# PixelController_V04.net
KiCad netlist of a schematic drawn in EAGLE
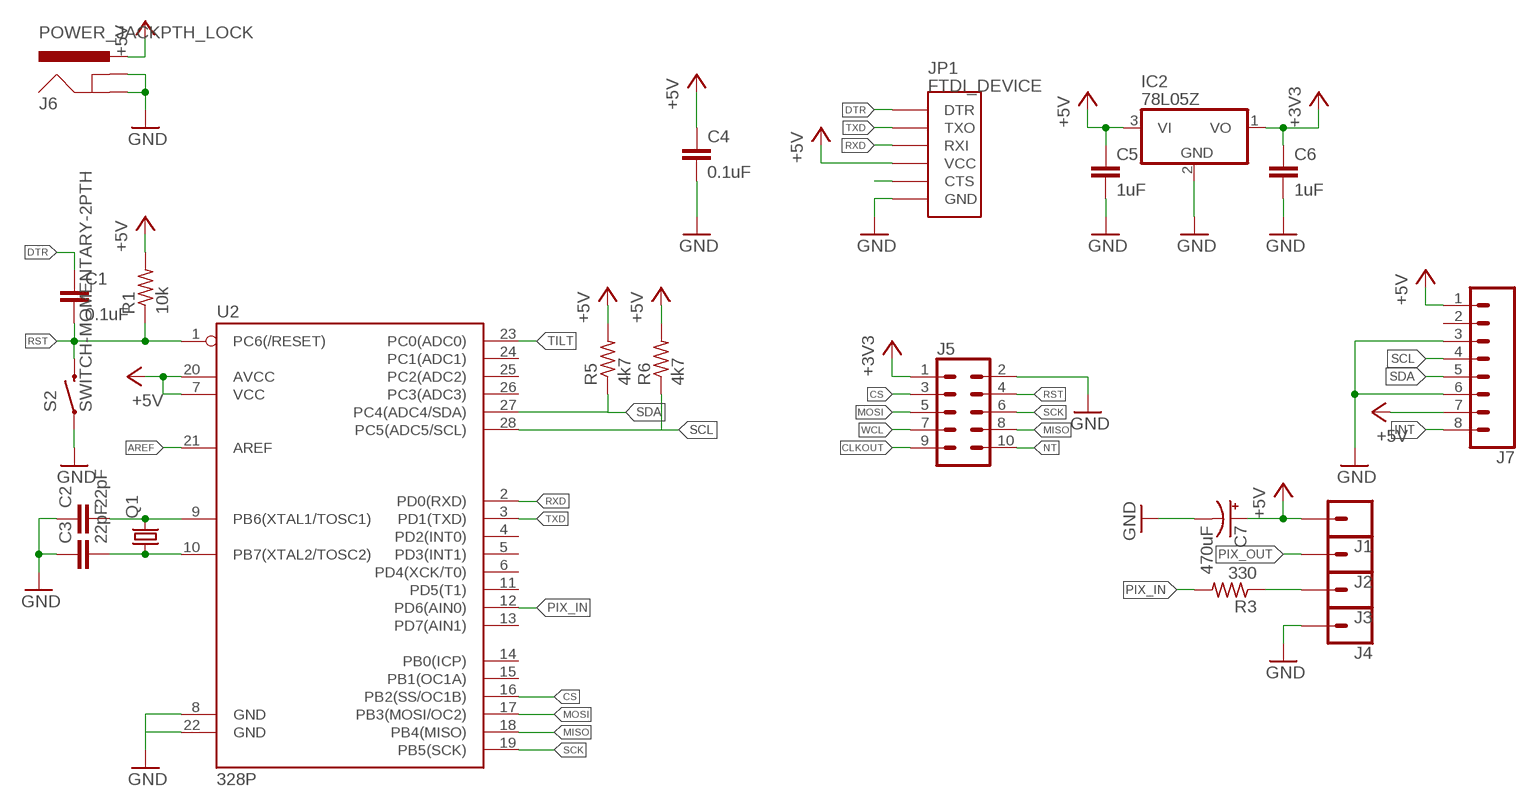
[diagram p0: schematic, sheet 1]

(export (version "E")
  (design (tool "Eeschema 10.0.6"))
  (components
    (comp (ref "C1")
      (value "0.1uF")
      (footprint "eagle-import:C050-025X075")
      (libsource (lib "eagle-import") (part "C-EU050-025X075"))
    )
    (comp (ref "C2")
      (value "22pF")
      (footprint "eagle-import:C050-024X044")
      (libsource (lib "eagle-import") (part "C-EU050-024X044"))
    )
    (comp (ref "C3")
      (value "22pF")
      (footprint "eagle-import:C050-024X044")
      (libsource (lib "eagle-import") (part "C-EU050-024X044"))
    )
    (comp (ref "C4")
      (value "0.1uF")
      (footprint "eagle-import:C050-025X075")
      (libsource (lib "eagle-import") (part "C-EU050-025X075"))
    )
    (comp (ref "C5")
      (value "1uF")
      (footprint "eagle-import:C050-025X075")
      (libsource (lib "eagle-import") (part "C-EU050-025X075"))
    )
    (comp (ref "C6")
      (value "1uF")
      (footprint "eagle-import:C050-025X075")
      (libsource (lib "eagle-import") (part "C-EU050-025X075"))
    )
    (comp (ref "C7")
      (value "470uF")
      (footprint "eagle-import:E3,5-8")
      (libsource (lib "eagle-import") (part "CPOL-USE3.5-8"))
    )
    (comp (ref "IC2")
      (value "78L05Z")
      (footprint "eagle-import:TO92")
      (libsource (lib "eagle-import") (part "78ZL05"))
    )
    (comp (ref "J1")
      (value "CONN_01")
      (footprint "eagle-import:1X01")
      (libsource (lib "eagle-import") (part "CONN_01"))
    )
    (comp (ref "J2")
      (value "CONN_01")
      (footprint "eagle-import:1X01")
      (libsource (lib "eagle-import") (part "CONN_01"))
    )
    (comp (ref "J3")
      (value "CONN_01")
      (footprint "eagle-import:1X01")
      (libsource (lib "eagle-import") (part "CONN_01"))
    )
    (comp (ref "J4")
      (value "CONN_01")
      (footprint "eagle-import:1X01")
      (libsource (lib "eagle-import") (part "CONN_01"))
    )
    (comp (ref "J5")
      (value "CONN_05X2PTH")
      (footprint "eagle-import:2X5")
      (libsource (lib "eagle-import") (part "CONN_05X2PTH"))
    )
    (comp (ref "J6")
      (value "POWER_JACKPTH_LOCK")
      (footprint "eagle-import:POWER_JACK_PTH_LOCK")
      (libsource (lib "eagle-import") (part "POWER_JACKPTH_LOCK"))
    )
    (comp (ref "J7")
      (value "CONN_08\"")
      (footprint "eagle-import:1X08@1")
      (libsource (lib "eagle-import") (part "CONN_08{dblquote}"))
    )
    (comp (ref "JP1")
      (value "FTDI_DEVICE")
      (footprint "eagle-import:FTDI_DEVICE_SIDE")
      (libsource (lib "eagle-import") (part "FTDI_DEVICE"))
    )
    (comp (ref "Q1")
      (value "CRYSTALHC49U70")
      (footprint "eagle-import:HC49U70")
      (libsource (lib "eagle-import") (part "CRYSTALHC49U70"))
    )
    (comp (ref "R1")
      (value "10k")
      (footprint "eagle-import:0204_7")
      (libsource (lib "eagle-import") (part "R-US_0204/7"))
    )
    (comp (ref "R3")
      (value "330")
      (footprint "eagle-import:0204_7")
      (libsource (lib "eagle-import") (part "R-US_0204/7"))
    )
    (comp (ref "R5")
      (value "4k7")
      (footprint "eagle-import:0204_7")
      (libsource (lib "eagle-import") (part "R-US_0204/7"))
    )
    (comp (ref "R6")
      (value "4k7")
      (footprint "eagle-import:0204_7")
      (libsource (lib "eagle-import") (part "R-US_0204/7"))
    )
    (comp (ref "S2")
      (value "SWITCH-MOMENTARY-2PTH")
      (footprint "eagle-import:TACTILE-PTH")
      (libsource (lib "eagle-import") (part "SWITCH-MOMENTARY-2PTH"))
    )
    (comp (ref "U2")
      (value "328P")
      (footprint "eagle-import:DIP28")
      (libsource (lib "eagle-import") (part "ATMEGA328P_PDIP"))
    )
  )
  (nets
    (net (code "1") (name "+3V3") (class "Default")
      (node (ref "C6") (pin "1") (pinfunction "1_1") (pintype "passive"))
      (node (ref "IC2") (pin "1") (pinfunction "VO_1") (pintype "passive"))
      (node (ref "J5") (pin "1") (pinfunction "1_1") (pintype "passive"))
    )
    (net (code "2") (name "+5V") (class "Default")
      (node (ref "C4") (pin "1") (pinfunction "1_1") (pintype "passive"))
      (node (ref "C5") (pin "1") (pinfunction "1_1") (pintype "passive"))
      (node (ref "C7") (pin "+") (pinfunction "+_+") (pintype "passive"))
      (node (ref "IC2") (pin "3") (pinfunction "VI_3") (pintype "input"))
      (node (ref "J1") (pin "1") (pinfunction "1_1") (pintype "passive"))
      (node (ref "J6") (pin "PWR") (pinfunction "PWR_PWR") (pintype "bidirectional"))
      (node (ref "J7") (pin "1") (pinfunction "1_1") (pintype "passive"))
      (node (ref "J7") (pin "7") (pinfunction "7_7") (pintype "passive"))
      (node (ref "JP1") (pin "P$4") (pinfunction "VCC_P$4") (pintype "bidirectional"))
      (node (ref "R1") (pin "2") (pinfunction "2_2") (pintype "passive"))
      (node (ref "R5") (pin "2") (pinfunction "2_2") (pintype "passive"))
      (node (ref "R6") (pin "2") (pinfunction "2_2") (pintype "passive"))
      (node (ref "U2") (pin "20") (pinfunction "AVCC_20") (pintype "bidirectional"))
      (node (ref "U2") (pin "7") (pinfunction "VCC_7") (pintype "bidirectional"))
    )
    (net (code "3") (name "AREF") (class "Default")
      (node (ref "U2") (pin "21") (pinfunction "AREF_21") (pintype "bidirectional"))
    )
    (net (code "4") (name "CLKOUT") (class "Default")
      (node (ref "J5") (pin "9") (pinfunction "9_9") (pintype "passive"))
    )
    (net (code "5") (name "CS") (class "Default")
      (node (ref "J5") (pin "3") (pinfunction "3_3") (pintype "passive"))
      (node (ref "U2") (pin "16") (pinfunction "PB2(SS/OC1B)_16") (pintype "bidirectional"))
    )
    (net (code "6") (name "DTR") (class "Default")
      (node (ref "C1") (pin "1") (pinfunction "1_1") (pintype "passive"))
      (node (ref "JP1") (pin "P$1") (pinfunction "DTR_P$1") (pintype "bidirectional"))
    )
    (net (code "7") (name "GND") (class "Default")
      (node (ref "C2") (pin "1") (pinfunction "1_1") (pintype "passive"))
      (node (ref "C3") (pin "1") (pinfunction "1_1") (pintype "passive"))
      (node (ref "C4") (pin "2") (pinfunction "2_2") (pintype "passive"))
      (node (ref "C5") (pin "2") (pinfunction "2_2") (pintype "passive"))
      (node (ref "C6") (pin "2") (pinfunction "2_2") (pintype "passive"))
      (node (ref "C7") (pin "-") (pinfunction "-_-") (pintype "passive"))
      (node (ref "IC2") (pin "2") (pinfunction "GND_2") (pintype "passive"))
      (node (ref "J4") (pin "1") (pinfunction "1_1") (pintype "passive"))
      (node (ref "J5") (pin "2") (pinfunction "2_2") (pintype "passive"))
      (node (ref "J6") (pin "GND") (pinfunction "GND_GND") (pintype "bidirectional"))
      (node (ref "J6") (pin "GNDBREAK") (pinfunction "GNDBREAK_GNDBREAK") (pintype "bidirectional"))
      (node (ref "J7") (pin "3") (pinfunction "3_3") (pintype "passive"))
      (node (ref "J7") (pin "6") (pinfunction "6_6") (pintype "passive"))
      (node (ref "JP1") (pin "P$6") (pinfunction "GND_P$6") (pintype "bidirectional"))
      (node (ref "S2") (pin "1") (pinfunction "1_1") (pintype "passive"))
      (node (ref "U2") (pin "22") (pinfunction "GND_22") (pintype "bidirectional"))
      (node (ref "U2") (pin "8") (pinfunction "GND_8") (pintype "bidirectional"))
    )
    (net (code "8") (name "INT") (class "Default")
      (node (ref "J7") (pin "8") (pinfunction "8_8") (pintype "passive"))
    )
    (net (code "9") (name "MISO") (class "Default")
      (node (ref "J5") (pin "8") (pinfunction "8_8") (pintype "passive"))
      (node (ref "U2") (pin "18") (pinfunction "PB4(MISO)_18") (pintype "bidirectional"))
    )
    (net (code "10") (name "MOSI") (class "Default")
      (node (ref "J5") (pin "5") (pinfunction "5_5") (pintype "passive"))
      (node (ref "U2") (pin "17") (pinfunction "PB3(MOSI/OC2)_17") (pintype "bidirectional"))
    )
    (net (code "11") (name "NT") (class "Default")
      (node (ref "J5") (pin "10") (pinfunction "10_10") (pintype "passive"))
    )
    (net (code "12") (name "Net-(J3-Pad1)") (class "Default")
      (node (ref "J3") (pin "1") (pinfunction "1_1") (pintype "passive"))
      (node (ref "R3") (pin "1") (pinfunction "1_1") (pintype "passive"))
    )
    (net (code "13") (name "Net-(U2-PB6(XTAL1{slash}TOSC1))") (class "Default")
      (node (ref "C2") (pin "2") (pinfunction "2_2") (pintype "passive"))
      (node (ref "Q1") (pin "2") (pinfunction "2_2") (pintype "passive"))
      (node (ref "U2") (pin "9") (pinfunction "PB6(XTAL1/TOSC1)_9") (pintype "bidirectional"))
    )
    (net (code "14") (name "Net-(U2-PB7(XTAL2{slash}TOSC2))") (class "Default")
      (node (ref "C3") (pin "2") (pinfunction "2_2") (pintype "passive"))
      (node (ref "Q1") (pin "1") (pinfunction "1_1") (pintype "passive"))
      (node (ref "U2") (pin "10") (pinfunction "PB7(XTAL2/TOSC2)_10") (pintype "bidirectional"))
    )
    (net (code "15") (name "PIX_IN") (class "Default")
      (node (ref "R3") (pin "2") (pinfunction "2_2") (pintype "passive"))
      (node (ref "U2") (pin "12") (pinfunction "PD6(AIN0)_12") (pintype "bidirectional"))
    )
    (net (code "16") (name "PIX_OUT") (class "Default")
      (node (ref "J2") (pin "1") (pinfunction "1_1") (pintype "passive"))
    )
    (net (code "17") (name "RST") (class "Default")
      (node (ref "C1") (pin "2") (pinfunction "2_2") (pintype "passive"))
      (node (ref "J5") (pin "4") (pinfunction "4_4") (pintype "passive"))
      (node (ref "R1") (pin "1") (pinfunction "1_1") (pintype "passive"))
      (node (ref "S2") (pin "3") (pinfunction "2_3") (pintype "passive"))
      (node (ref "U2") (pin "1") (pinfunction "PC6(/RESET)_1") (pintype "bidirectional"))
    )
    (net (code "18") (name "RXD") (class "Default")
      (node (ref "JP1") (pin "P$3") (pinfunction "RXI_P$3") (pintype "bidirectional"))
      (node (ref "U2") (pin "2") (pinfunction "PD0(RXD)_2") (pintype "bidirectional"))
    )
    (net (code "19") (name "SCK") (class "Default")
      (node (ref "J5") (pin "6") (pinfunction "6_6") (pintype "passive"))
      (node (ref "U2") (pin "19") (pinfunction "PB5(SCK)_19") (pintype "bidirectional"))
    )
    (net (code "20") (name "SCL") (class "Default")
      (node (ref "J7") (pin "4") (pinfunction "4_4") (pintype "passive"))
      (node (ref "R6") (pin "1") (pinfunction "1_1") (pintype "passive"))
      (node (ref "U2") (pin "28") (pinfunction "PC5(ADC5/SCL)_28") (pintype "bidirectional"))
    )
    (net (code "21") (name "SDA") (class "Default")
      (node (ref "J7") (pin "5") (pinfunction "5_5") (pintype "passive"))
      (node (ref "R5") (pin "1") (pinfunction "1_1") (pintype "passive"))
      (node (ref "U2") (pin "27") (pinfunction "PC4(ADC4/SDA)_27") (pintype "bidirectional"))
    )
    (net (code "22") (name "TILT") (class "Default")
      (node (ref "U2") (pin "23") (pinfunction "PC0(ADC0)_23") (pintype "bidirectional"))
    )
    (net (code "23") (name "TXD") (class "Default")
      (node (ref "JP1") (pin "P$2") (pinfunction "TXO_P$2") (pintype "bidirectional"))
      (node (ref "U2") (pin "3") (pinfunction "PD1(TXD)_3") (pintype "bidirectional"))
    )
    (net (code "24") (name "WCL") (class "Default")
      (node (ref "J5") (pin "7") (pinfunction "7_7") (pintype "passive"))
    )
    (net (code "25") (name "unconnected-(J7-Pad2)") (class "Default")
      (node (ref "J7") (pin "2") (pinfunction "2_2") (pintype "passive"))
    )
    (net (code "26") (name "unconnected-(JP1-CTS-PadP$5)") (class "Default")
      (node (ref "JP1") (pin "P$5") (pinfunction "CTS_P$5") (pintype "bidirectional"))
    )
    (net (code "27") (name "unconnected-(U2-PB0(ICP)-Pad14)") (class "Default")
      (node (ref "U2") (pin "14") (pinfunction "PB0(ICP)_14") (pintype "bidirectional"))
    )
    (net (code "28") (name "unconnected-(U2-PB1(OC1A)-Pad15)") (class "Default")
      (node (ref "U2") (pin "15") (pinfunction "PB1(OC1A)_15") (pintype "bidirectional"))
    )
    (net (code "29") (name "unconnected-(U2-PC1(ADC1)-Pad24)") (class "Default")
      (node (ref "U2") (pin "24") (pinfunction "PC1(ADC1)_24") (pintype "bidirectional"))
    )
    (net (code "30") (name "unconnected-(U2-PC2(ADC2)-Pad25)") (class "Default")
      (node (ref "U2") (pin "25") (pinfunction "PC2(ADC2)_25") (pintype "bidirectional"))
    )
    (net (code "31") (name "unconnected-(U2-PC3(ADC3)-Pad26)") (class "Default")
      (node (ref "U2") (pin "26") (pinfunction "PC3(ADC3)_26") (pintype "bidirectional"))
    )
    (net (code "32") (name "unconnected-(U2-PD2(INT0)-Pad4)") (class "Default")
      (node (ref "U2") (pin "4") (pinfunction "PD2(INT0)_4") (pintype "bidirectional"))
    )
    (net (code "33") (name "unconnected-(U2-PD3(INT1)-Pad5)") (class "Default")
      (node (ref "U2") (pin "5") (pinfunction "PD3(INT1)_5") (pintype "bidirectional"))
    )
    (net (code "34") (name "unconnected-(U2-PD4(XCK{slash}T0)-Pad6)") (class "Default")
      (node (ref "U2") (pin "6") (pinfunction "PD4(XCK/T0)_6") (pintype "bidirectional"))
    )
    (net (code "35") (name "unconnected-(U2-PD5(T1)-Pad11)") (class "Default")
      (node (ref "U2") (pin "11") (pinfunction "PD5(T1)_11") (pintype "bidirectional"))
    )
    (net (code "36") (name "unconnected-(U2-PD7(AIN1)-Pad13)") (class "Default")
      (node (ref "U2") (pin "13") (pinfunction "PD7(AIN1)_13") (pintype "bidirectional"))
    )
  )
)
